# WIFI_BT.net
KiCad netlist of a schematic drawn in Altium Designer
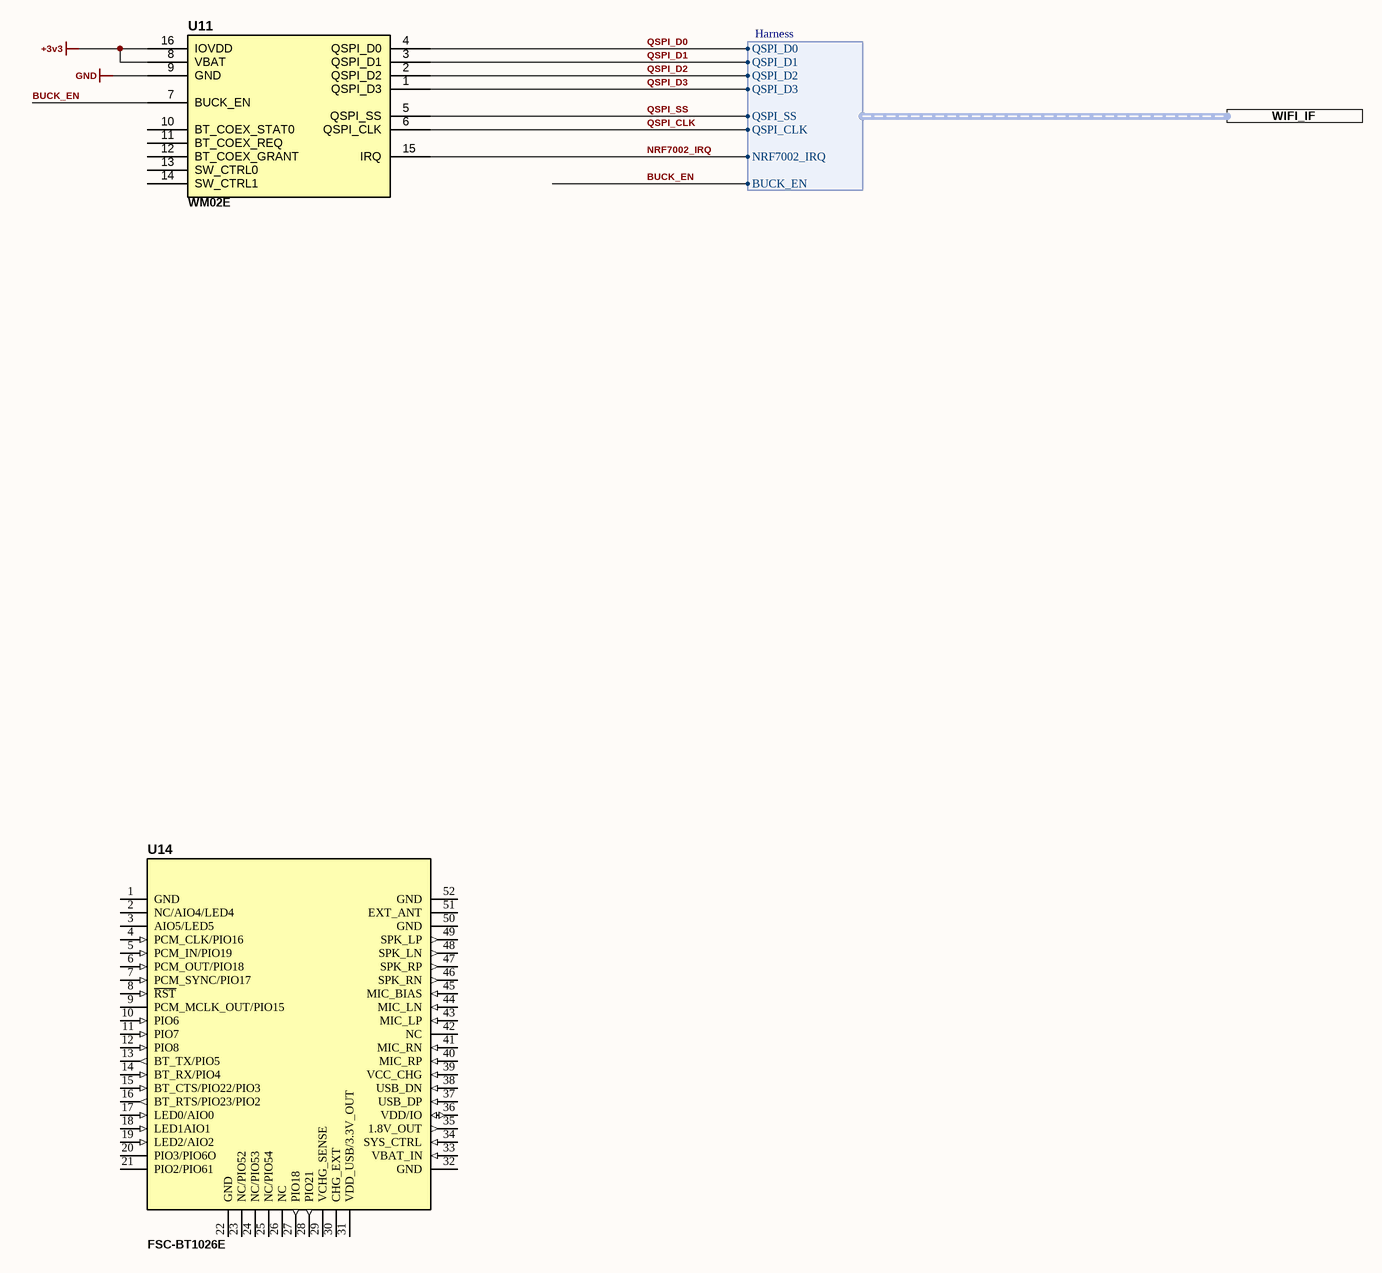
[diagram p0: WIFI_BT.SchDoc]

(export (version "E")
  (design (tool "Eeschema 10.0.6"))
  (components
    (comp (ref "U11")
      (value "WM02E")
      (footprint "WM02E")
      (description "NRF7002 Module")
      (fields (field (name "MANUFACTURER") "Fanstel"))
      (libsource (lib "eModule") (part "WM02E"))
    )
    (comp (ref "U14")
      (value "FSC-BT1026E")
      (footprint "FSC-BT1026x")
      (description "Bluetooth 5.1 dual mode audio module")
      (fields (field (name "MANUFACTURER") "FEASYCOM"))
      (libsource (lib "eAudio") (part "FSC-BT1026E"))
    )
  )
  (nets
    (net (code "2") (name "+3v3") (class "Default")
      (node (ref "U11") (pin "16") (pinfunction "IOVDD_16") (pintype "passive"))
      (node (ref "U11") (pin "8") (pinfunction "VBAT_8") (pintype "passive"))
    )
    (net (code "3") (name "/BUCK_EN") (class "Default")
      (node (ref "U11") (pin "7") (pinfunction "BUCK_EN_7") (pintype "passive"))
    )
    (net (code "4") (name "/NRF7002_IRQ") (class "Default")
      (node (ref "U11") (pin "15") (pinfunction "IRQ_15") (pintype "passive"))
    )
    (net (code "5") (name "/QSPI_CLK") (class "Default")
      (node (ref "U11") (pin "6") (pinfunction "QSPI_CLK_6") (pintype "passive"))
    )
    (net (code "6") (name "/QSPI_D0") (class "Default")
      (node (ref "U11") (pin "4") (pinfunction "QSPI_D0_4") (pintype "passive"))
    )
    (net (code "7") (name "/QSPI_D1") (class "Default")
      (node (ref "U11") (pin "3") (pinfunction "QSPI_D1_3") (pintype "passive"))
    )
    (net (code "8") (name "/QSPI_D2") (class "Default")
      (node (ref "U11") (pin "2") (pinfunction "QSPI_D2_2") (pintype "passive"))
    )
    (net (code "9") (name "/QSPI_D3") (class "Default")
      (node (ref "U11") (pin "1") (pinfunction "QSPI_D3_1") (pintype "passive"))
    )
    (net (code "10") (name "/QSPI_SS") (class "Default")
      (node (ref "U11") (pin "5") (pinfunction "QSPI_SS_5") (pintype "passive"))
    )
    (net (code "12") (name "GND") (class "Default")
      (node (ref "U11") (pin "9") (pinfunction "GND_9") (pintype "passive"))
    )
    (net (code "13") (name "unconnected-(U11-BT_COEX_GRANT-Pad12)") (class "Default")
      (node (ref "U11") (pin "12") (pinfunction "BT_COEX_GRANT_12") (pintype "passive"))
    )
    (net (code "14") (name "unconnected-(U11-BT_COEX_REQ-Pad11)") (class "Default")
      (node (ref "U11") (pin "11") (pinfunction "BT_COEX_REQ_11") (pintype "passive"))
    )
    (net (code "15") (name "unconnected-(U11-BT_COEX_STAT0-Pad10)") (class "Default")
      (node (ref "U11") (pin "10") (pinfunction "BT_COEX_STAT0_10") (pintype "passive"))
    )
    (net (code "16") (name "unconnected-(U11-SW_CTRL0-Pad13)") (class "Default")
      (node (ref "U11") (pin "13") (pinfunction "SW_CTRL0_13") (pintype "passive"))
    )
    (net (code "17") (name "unconnected-(U11-SW_CTRL1-Pad14)") (class "Default")
      (node (ref "U11") (pin "14") (pinfunction "SW_CTRL1_14") (pintype "passive"))
    )
    (net (code "18") (name "unconnected-(U14-1.8V_OUT-Pad35)") (class "Default")
      (node (ref "U14") (pin "35") (pinfunction "1.8V_OUT_35") (pintype "output"))
    )
    (net (code "19") (name "unconnected-(U14-AIO5{slash}LED5-Pad3)") (class "Default")
      (node (ref "U14") (pin "3") (pinfunction "AIO5/LED5_3") (pintype "power_in"))
    )
    (net (code "20") (name "unconnected-(U14-BT_CTS{slash}PIO22{slash}PIO3-Pad15)") (class "Default")
      (node (ref "U14") (pin "15") (pinfunction "BT_CTS/PIO22/PIO3_15") (pintype "input"))
    )
    (net (code "21") (name "unconnected-(U14-BT_RTS{slash}PIO23{slash}PIO2-Pad16)") (class "Default")
      (node (ref "U14") (pin "16") (pinfunction "BT_RTS/PIO23/PIO2_16") (pintype "output"))
    )
    (net (code "22") (name "unconnected-(U14-BT_RX{slash}PIO4-Pad14)") (class "Default")
      (node (ref "U14") (pin "14") (pinfunction "BT_RX/PIO4_14") (pintype "input"))
    )
    (net (code "23") (name "unconnected-(U14-BT_TX{slash}PIO5-Pad13)") (class "Default")
      (node (ref "U14") (pin "13") (pinfunction "BT_TX/PIO5_13") (pintype "output"))
    )
    (net (code "24") (name "unconnected-(U14-CHG_EXT-Pad30)") (class "Default")
      (node (ref "U14") (pin "30") (pinfunction "CHG_EXT_30") (pintype "power_in"))
    )
    (net (code "25") (name "unconnected-(U14-EXT_ANT-Pad51)") (class "Default")
      (node (ref "U14") (pin "51") (pinfunction "EXT_ANT_51") (pintype "power_in"))
    )
    (net (code "26") (name "unconnected-(U14-GND-Pad1)") (class "Default")
      (node (ref "U14") (pin "1") (pinfunction "GND_1") (pintype "power_in"))
    )
    (net (code "27") (name "unconnected-(U14-GND-Pad22)") (class "Default")
      (node (ref "U14") (pin "22") (pinfunction "GND_22") (pintype "power_in"))
    )
    (net (code "28") (name "unconnected-(U14-GND-Pad32)") (class "Default")
      (node (ref "U14") (pin "32") (pinfunction "GND_32") (pintype "power_in"))
    )
    (net (code "29") (name "unconnected-(U14-GND-Pad50)") (class "Default")
      (node (ref "U14") (pin "50") (pinfunction "GND_50") (pintype "power_in"))
    )
    (net (code "30") (name "unconnected-(U14-GND-Pad52)") (class "Default")
      (node (ref "U14") (pin "52") (pinfunction "GND_52") (pintype "power_in"))
    )
    (net (code "31") (name "unconnected-(U14-LED0{slash}AIO0-Pad17)") (class "Default")
      (node (ref "U14") (pin "17") (pinfunction "LED0/AIO0_17") (pintype "input"))
    )
    (net (code "32") (name "unconnected-(U14-LED1AIO1-Pad18)") (class "Default")
      (node (ref "U14") (pin "18") (pinfunction "LED1AIO1_18") (pintype "input"))
    )
    (net (code "33") (name "unconnected-(U14-LED2{slash}AIO2-Pad19)") (class "Default")
      (node (ref "U14") (pin "19") (pinfunction "LED2/AIO2_19") (pintype "input"))
    )
    (net (code "34") (name "unconnected-(U14-MIC_BIAS-Pad45)") (class "Default")
      (node (ref "U14") (pin "45") (pinfunction "MIC_BIAS_45") (pintype "input"))
    )
    (net (code "35") (name "unconnected-(U14-MIC_LN-Pad44)") (class "Default")
      (node (ref "U14") (pin "44") (pinfunction "MIC_LN_44") (pintype "input"))
    )
    (net (code "36") (name "unconnected-(U14-MIC_LP-Pad43)") (class "Default")
      (node (ref "U14") (pin "43") (pinfunction "MIC_LP_43") (pintype "input"))
    )
    (net (code "37") (name "unconnected-(U14-MIC_RN-Pad41)") (class "Default")
      (node (ref "U14") (pin "41") (pinfunction "MIC_RN_41") (pintype "input"))
    )
    (net (code "38") (name "unconnected-(U14-MIC_RP-Pad40)") (class "Default")
      (node (ref "U14") (pin "40") (pinfunction "MIC_RP_40") (pintype "input"))
    )
    (net (code "39") (name "unconnected-(U14-NC-Pad26)") (class "Default")
      (node (ref "U14") (pin "26") (pinfunction "NC_26") (pintype "power_in"))
    )
    (net (code "40") (name "unconnected-(U14-NC-Pad42)") (class "Default")
      (node (ref "U14") (pin "42") (pinfunction "NC_42") (pintype "power_in"))
    )
    (net (code "41") (name "unconnected-(U14-NC{slash}AIO4{slash}LED4-Pad2)") (class "Default")
      (node (ref "U14") (pin "2") (pinfunction "NC/AIO4/LED4_2") (pintype "power_in"))
    )
    (net (code "42") (name "unconnected-(U14-NC{slash}PIO52-Pad23)") (class "Default")
      (node (ref "U14") (pin "23") (pinfunction "NC/PIO52_23") (pintype "power_in"))
    )
    (net (code "43") (name "unconnected-(U14-NC{slash}PIO53-Pad24)") (class "Default")
      (node (ref "U14") (pin "24") (pinfunction "NC/PIO53_24") (pintype "power_in"))
    )
    (net (code "44") (name "unconnected-(U14-NC{slash}PIO54-Pad25)") (class "Default")
      (node (ref "U14") (pin "25") (pinfunction "NC/PIO54_25") (pintype "power_in"))
    )
    (net (code "45") (name "unconnected-(U14-PCM_CLK{slash}PIO16-Pad4)") (class "Default")
      (node (ref "U14") (pin "4") (pinfunction "PCM_CLK/PIO16_4") (pintype "input"))
    )
    (net (code "46") (name "unconnected-(U14-PCM_IN{slash}PIO19-Pad5)") (class "Default")
      (node (ref "U14") (pin "5") (pinfunction "PCM_IN/PIO19_5") (pintype "input"))
    )
    (net (code "47") (name "unconnected-(U14-PCM_MCLK_OUT{slash}PIO15-Pad9)") (class "Default")
      (node (ref "U14") (pin "9") (pinfunction "PCM_MCLK_OUT/PIO15_9") (pintype "power_in"))
    )
    (net (code "48") (name "unconnected-(U14-PCM_OUT{slash}PIO18-Pad6)") (class "Default")
      (node (ref "U14") (pin "6") (pinfunction "PCM_OUT/PIO18_6") (pintype "input"))
    )
    (net (code "49") (name "unconnected-(U14-PCM_SYNC{slash}PIO17-Pad7)") (class "Default")
      (node (ref "U14") (pin "7") (pinfunction "PCM_SYNC/PIO17_7") (pintype "input"))
    )
    (net (code "50") (name "unconnected-(U14-PIO2{slash}PIO61-Pad21)") (class "Default")
      (node (ref "U14") (pin "21") (pinfunction "PIO2/PIO61_21") (pintype "power_in"))
    )
    (net (code "51") (name "unconnected-(U14-PIO3{slash}PIO6O-Pad20)") (class "Default")
      (node (ref "U14") (pin "20") (pinfunction "PIO3/PIO6O_20") (pintype "power_in"))
    )
    (net (code "52") (name "unconnected-(U14-PIO6-Pad10)") (class "Default")
      (node (ref "U14") (pin "10") (pinfunction "PIO6_10") (pintype "input"))
    )
    (net (code "53") (name "unconnected-(U14-PIO7-Pad11)") (class "Default")
      (node (ref "U14") (pin "11") (pinfunction "PIO7_11") (pintype "input"))
    )
    (net (code "54") (name "unconnected-(U14-PIO8-Pad12)") (class "Default")
      (node (ref "U14") (pin "12") (pinfunction "PIO8_12") (pintype "input"))
    )
    (net (code "55") (name "unconnected-(U14-PIO18-Pad27)") (class "Default")
      (node (ref "U14") (pin "27") (pinfunction "PIO18_27") (pintype "output"))
    )
    (net (code "56") (name "unconnected-(U14-PIO21-Pad28)") (class "Default")
      (node (ref "U14") (pin "28") (pinfunction "PIO21_28") (pintype "output"))
    )
    (net (code "57") (name "unconnected-(U14-SPK_LN-Pad48)") (class "Default")
      (node (ref "U14") (pin "48") (pinfunction "SPK_LN_48") (pintype "output"))
    )
    (net (code "58") (name "unconnected-(U14-SPK_LP-Pad49)") (class "Default")
      (node (ref "U14") (pin "49") (pinfunction "SPK_LP_49") (pintype "output"))
    )
    (net (code "59") (name "unconnected-(U14-SPK_RN-Pad46)") (class "Default")
      (node (ref "U14") (pin "46") (pinfunction "SPK_RN_46") (pintype "output"))
    )
    (net (code "60") (name "unconnected-(U14-SPK_RP-Pad47)") (class "Default")
      (node (ref "U14") (pin "47") (pinfunction "SPK_RP_47") (pintype "output"))
    )
    (net (code "61") (name "unconnected-(U14-SYS_CTRL-Pad34)") (class "Default")
      (node (ref "U14") (pin "34") (pinfunction "SYS_CTRL_34") (pintype "input"))
    )
    (net (code "62") (name "unconnected-(U14-USB_DN-Pad38)") (class "Default")
      (node (ref "U14") (pin "38") (pinfunction "USB_DN_38") (pintype "input"))
    )
    (net (code "63") (name "unconnected-(U14-USB_DP-Pad37)") (class "Default")
      (node (ref "U14") (pin "37") (pinfunction "USB_DP_37") (pintype "input"))
    )
    (net (code "64") (name "unconnected-(U14-VBAT_IN-Pad33)") (class "Default")
      (node (ref "U14") (pin "33") (pinfunction "VBAT_IN_33") (pintype "input"))
    )
    (net (code "65") (name "unconnected-(U14-VCC_CHG-Pad39)") (class "Default")
      (node (ref "U14") (pin "39") (pinfunction "VCC_CHG_39") (pintype "input"))
    )
    (net (code "66") (name "unconnected-(U14-VCHG_SENSE-Pad29)") (class "Default")
      (node (ref "U14") (pin "29") (pinfunction "VCHG_SENSE_29") (pintype "power_in"))
    )
    (net (code "67") (name "unconnected-(U14-VDD_USB{slash}3.3V_OUT-Pad31)") (class "Default")
      (node (ref "U14") (pin "31") (pinfunction "VDD_USB/3.3V_OUT_31") (pintype "power_in"))
    )
    (net (code "68") (name "unconnected-(U14-VDD{slash}IO-Pad36)") (class "Default")
      (node (ref "U14") (pin "36") (pinfunction "VDD/IO_36") (pintype "bidirectional"))
    )
    (net (code "69") (name "unconnected-(U14-~{RST}-Pad8)") (class "Default")
      (node (ref "U14") (pin "8") (pinfunction "~{RST}_8") (pintype "input"))
    )
  )
)
